# BLE-2541.net
KiCad netlist of a schematic drawn in Altium Designer
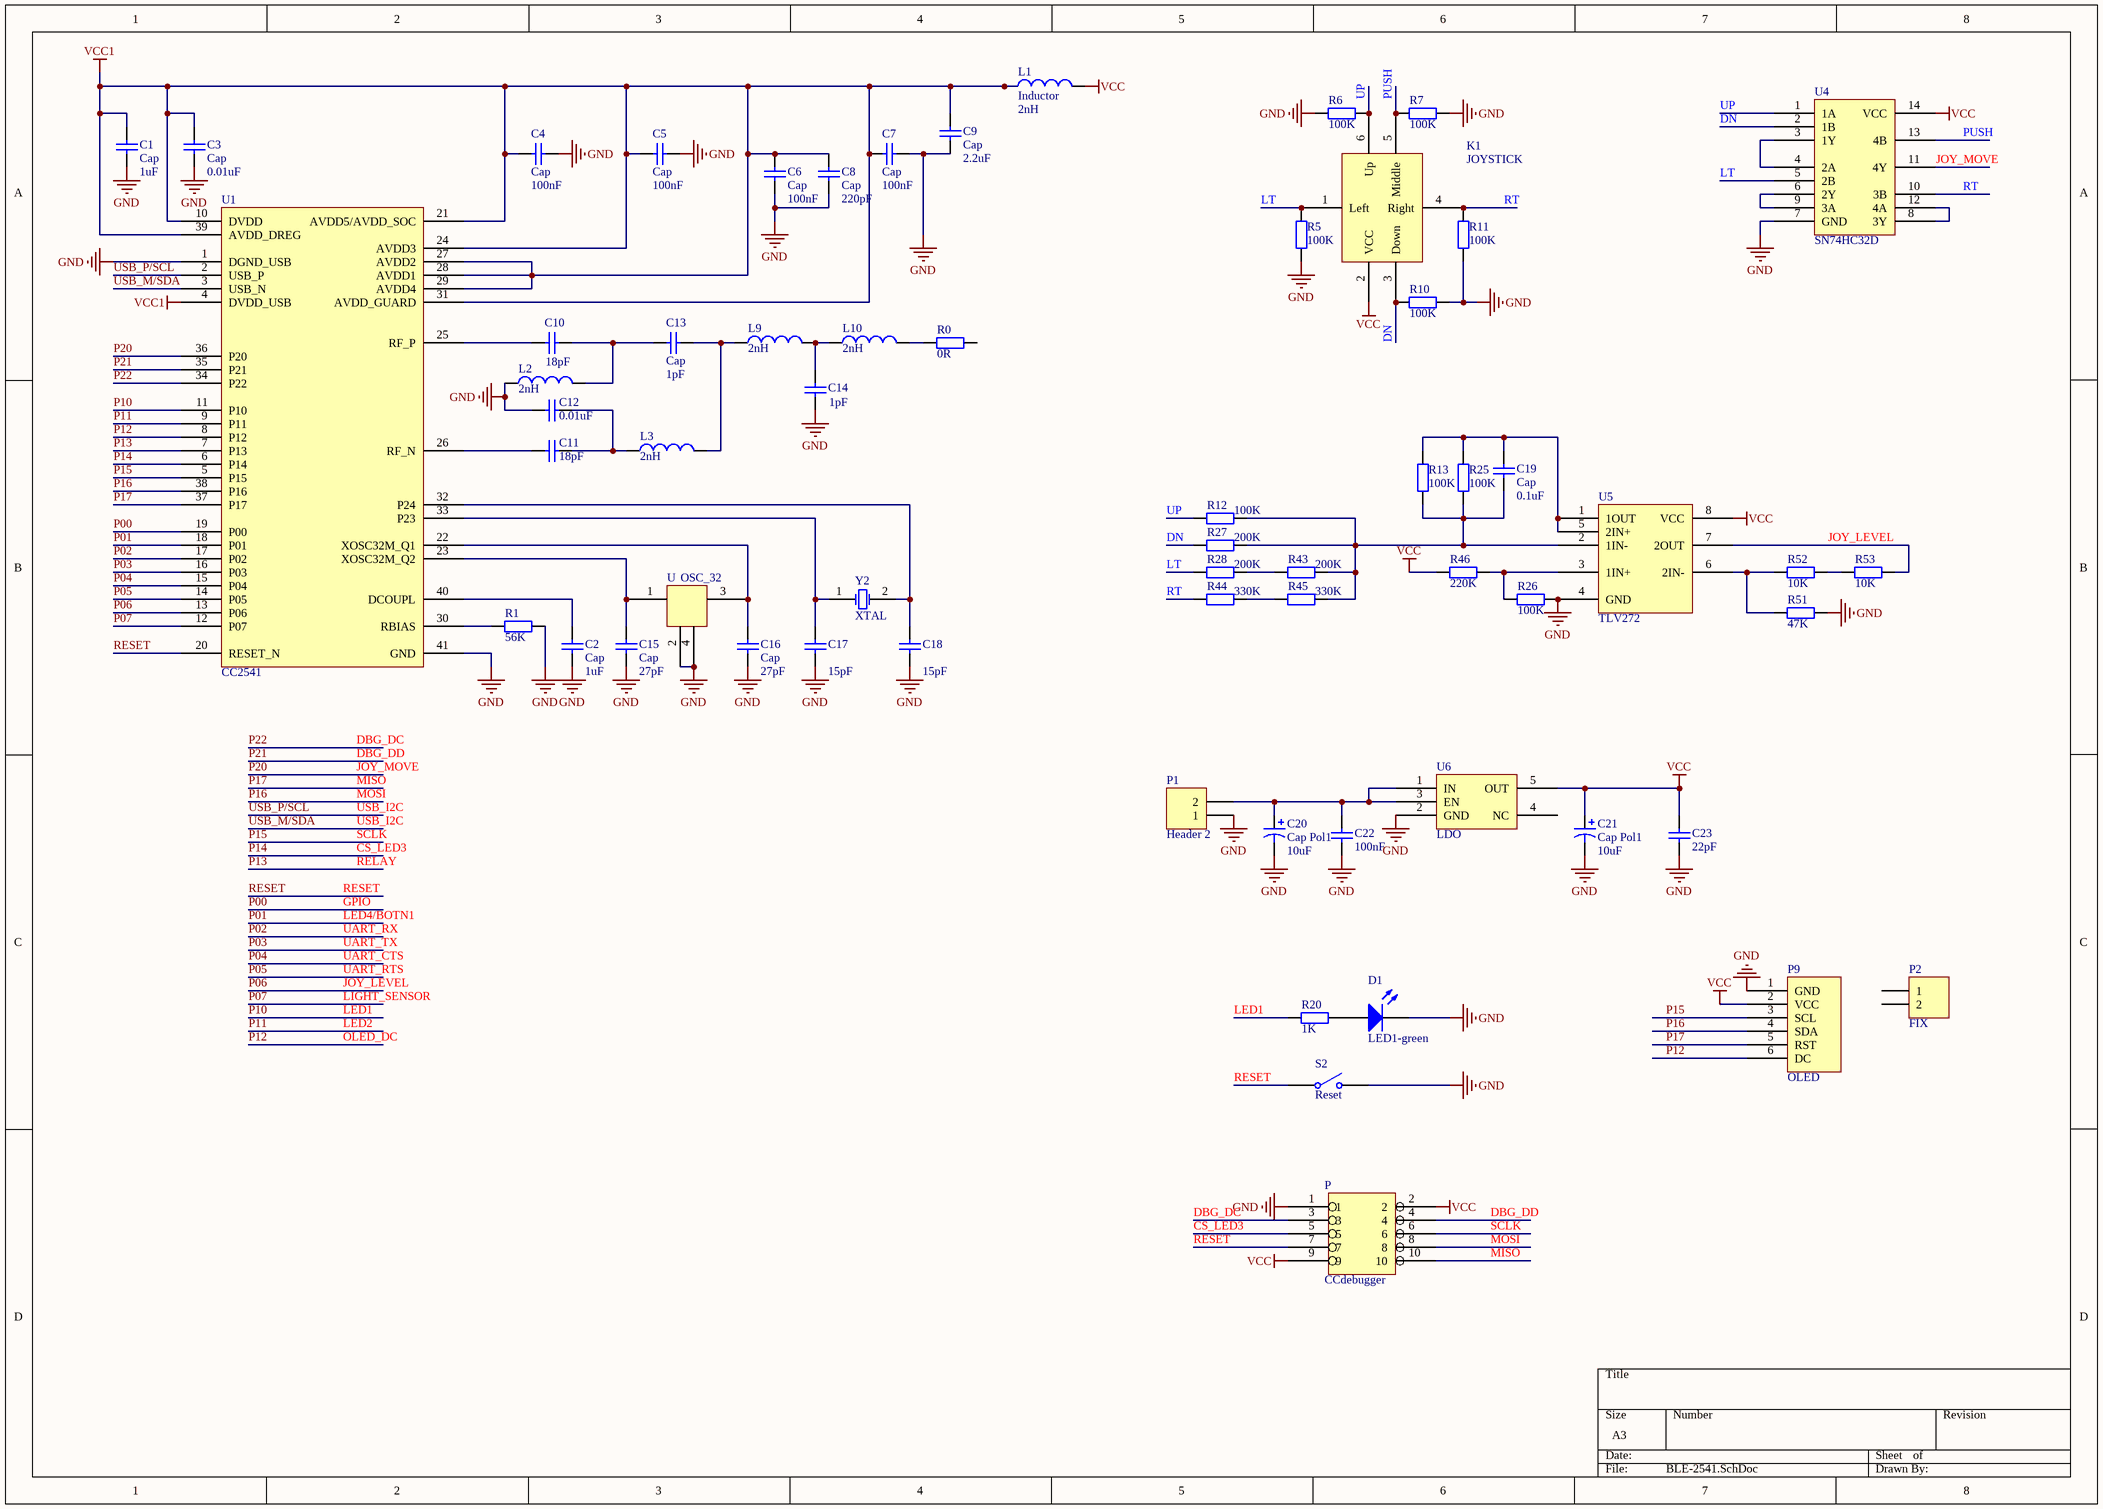
[diagram p0: BLE-2541.SchDoc]

(export (version "E")
  (design (tool "Eeschema 10.0.6"))
  (components
    (comp (ref "C1")
      (value "Cap")
      (footprint "RAD-0.3")
      (description "Capacitor")
      (fields (field (name "ALTIUM_VALUE") "1uF") (field (name "PUBLISHER") "Altium Limited"))
      (libsource (lib "Miscellaneous Devices") (part "Cap"))
    )
    (comp (ref "C2")
      (value "Cap")
      (footprint "RAD-0.3")
      (description "Capacitor")
      (fields (field (name "ALTIUM_VALUE") "1uF") (field (name "PUBLISHER") "Altium Limited"))
      (libsource (lib "Miscellaneous Devices") (part "Cap"))
    )
    (comp (ref "C3")
      (value "Cap")
      (footprint "RAD-0.3")
      (description "Capacitor")
      (fields (field (name "ALTIUM_VALUE") "0.01uF") (field (name "PUBLISHER") "Altium Limited"))
      (libsource (lib "Miscellaneous Devices") (part "Cap"))
    )
    (comp (ref "C4")
      (value "Cap")
      (footprint "RAD-0.3")
      (description "Capacitor")
      (fields (field (name "ALTIUM_VALUE") "100nF") (field (name "PUBLISHER") "Altium Limited"))
      (libsource (lib "Miscellaneous Devices") (part "Cap"))
    )
    (comp (ref "C5")
      (value "Cap")
      (footprint "RAD-0.3")
      (description "Capacitor")
      (fields (field (name "ALTIUM_VALUE") "100nF") (field (name "PUBLISHER") "Altium Limited"))
      (libsource (lib "Miscellaneous Devices") (part "Cap"))
    )
    (comp (ref "C6")
      (value "Cap")
      (footprint "RAD-0.3")
      (description "Capacitor")
      (fields (field (name "ALTIUM_VALUE") "100nF") (field (name "PUBLISHER") "Altium Limited"))
      (libsource (lib "Miscellaneous Devices") (part "Cap"))
    )
    (comp (ref "C7")
      (value "Cap")
      (footprint "RAD-0.3")
      (description "Capacitor")
      (fields (field (name "ALTIUM_VALUE") "100nF") (field (name "PUBLISHER") "Altium Limited"))
      (libsource (lib "Miscellaneous Devices") (part "Cap"))
    )
    (comp (ref "C8")
      (value "Cap")
      (footprint "RAD-0.3")
      (description "Capacitor")
      (fields (field (name "ALTIUM_VALUE") "220pF") (field (name "PUBLISHER") "Altium Limited"))
      (libsource (lib "Miscellaneous Devices") (part "Cap"))
    )
    (comp (ref "C9")
      (value "Cap")
      (footprint "RAD-0.3")
      (description "Capacitor")
      (fields (field (name "ALTIUM_VALUE") "2.2uF") (field (name "PUBLISHER") "Altium Limited"))
      (libsource (lib "Miscellaneous Devices") (part "Cap"))
    )
    (comp (ref "C10")
      (value "18pF")
      (footprint "RAD-0.3")
      (description "Capacitor")
      (fields (field (name "Comment") "Cap") (field (name "PUBLISHER") "Altium Limited"))
      (libsource (lib "Miscellaneous Devices") (part "Cap"))
    )
    (comp (ref "C11")
      (value "18pF")
      (footprint "RAD-0.3")
      (description "Capacitor")
      (fields (field (name "Comment") "Cap") (field (name "PUBLISHER") "Altium Limited"))
      (libsource (lib "Miscellaneous Devices") (part "Cap"))
    )
    (comp (ref "C12")
      (value "0.01uF")
      (footprint "RAD-0.3")
      (description "Capacitor")
      (fields (field (name "Comment") "Cap") (field (name "PUBLISHER") "Altium Limited"))
      (libsource (lib "Miscellaneous Devices") (part "Cap"))
    )
    (comp (ref "C13")
      (value "Cap")
      (footprint "RAD-0.3")
      (description "Capacitor")
      (fields (field (name "ALTIUM_VALUE") "1pF") (field (name "PUBLISHER") "Altium Limited"))
      (libsource (lib "Miscellaneous Devices") (part "Cap"))
    )
    (comp (ref "C14")
      (value "1pF")
      (footprint "RAD-0.3")
      (description "Capacitor")
      (fields (field (name "Comment") "Cap") (field (name "PUBLISHER") "Altium Limited"))
      (libsource (lib "Miscellaneous Devices") (part "Cap"))
    )
    (comp (ref "C15")
      (value "Cap")
      (footprint "RAD-0.3")
      (description "Capacitor")
      (fields (field (name "ALTIUM_VALUE") "27pF") (field (name "PUBLISHER") "Altium Limited"))
      (libsource (lib "Miscellaneous Devices") (part "Cap"))
    )
    (comp (ref "C16")
      (value "Cap")
      (footprint "RAD-0.3")
      (description "Capacitor")
      (fields (field (name "ALTIUM_VALUE") "27pF") (field (name "PUBLISHER") "Altium Limited"))
      (libsource (lib "Miscellaneous Devices") (part "Cap"))
    )
    (comp (ref "C17")
      (value "15pF")
      (footprint "RAD-0.3")
      (description "Capacitor")
      (fields (field (name "Comment") "Cap") (field (name "PUBLISHER") "Altium Limited"))
      (libsource (lib "Miscellaneous Devices") (part "Cap"))
    )
    (comp (ref "C18")
      (value "15pF")
      (footprint "RAD-0.3")
      (description "Capacitor")
      (fields (field (name "Comment") "Cap") (field (name "PUBLISHER") "Altium Limited"))
      (libsource (lib "Miscellaneous Devices") (part "Cap"))
    )
    (comp (ref "C19")
      (value "Cap")
      (footprint "RAD-0.3")
      (description "Capacitor")
      (fields (field (name "ALTIUM_VALUE") "0.1uF") (field (name "PUBLISHER") "Altium Limited"))
      (libsource (lib "Miscellaneous Devices") (part "Cap"))
    )
    (comp (ref "C20")
      (value "Cap Pol1")
      (footprint "RB7.6-15")
      (description "Polarized Capacitor (Radial)")
      (fields (field (name "ALTIUM_VALUE") "10uF") (field (name "PUBLISHER") "Altium Limited"))
      (libsource (lib "Miscellaneous Devices") (part "Cap Pol1"))
    )
    (comp (ref "C21")
      (value "Cap Pol1")
      (footprint "RB7.6-15")
      (description "Polarized Capacitor (Radial)")
      (fields (field (name "ALTIUM_VALUE") "10uF") (field (name "PUBLISHER") "Altium Limited"))
      (libsource (lib "Miscellaneous Devices") (part "Cap Pol1"))
    )
    (comp (ref "C22")
      (value "100nF")
      (footprint "RAD-0.3")
      (description "Capacitor")
      (fields (field (name "Comment") "Cap") (field (name "PUBLISHER") "Altium Limited"))
      (libsource (lib "Miscellaneous Devices") (part "Cap"))
    )
    (comp (ref "C23")
      (value "22pF")
      (footprint "RAD-0.3")
      (description "Capacitor")
      (fields (field (name "Comment") "Cap") (field (name "PUBLISHER") "Altium Limited"))
      (libsource (lib "Miscellaneous Devices") (part "Cap"))
    )
    (comp (ref "D1")
      (value "LED1-green")
      (footprint "3.2X1.6X1.1")
      (description "Typical RED, GREEN, YELLOW, AMBER GaAs LED")
      (fields (field (name "PUBLISHER") "Altium Limited"))
      (libsource (lib "Miscellaneous Devices") (part "LED2"))
    )
    (comp (ref "K1") (value "JOYSTICK") (libsource (lib "Schlib1") (part "JOYSTICK")))
    (comp (ref "L1")
      (value "Inductor")
      (footprint "0402-A")
      (fields (field (name "ALTIUM_VALUE") "2nH") (field (name "PUBLISHER") "Altium Limited"))
      (libsource (lib "Miscellaneous Devices") (part "Inductor"))
    )
    (comp (ref "L2")
      (value "2nH")
      (footprint "0402-A")
      (description "Inductor")
      (fields (field (name "PUBLISHER") "Altium Limited"))
      (libsource (lib "Miscellaneous Devices") (part "Inductor"))
    )
    (comp (ref "L3")
      (value "2nH")
      (footprint "0402-A")
      (description "Inductor")
      (fields (field (name "PUBLISHER") "Altium Limited"))
      (libsource (lib "Miscellaneous Devices") (part "Inductor"))
    )
    (comp (ref "L9")
      (value "2nH")
      (footprint "0402-A")
      (description "Inductor")
      (fields (field (name "PUBLISHER") "Altium Limited"))
      (libsource (lib "Miscellaneous Devices") (part "Inductor"))
    )
    (comp (ref "L10")
      (value "2nH")
      (footprint "0402-A")
      (description "Inductor")
      (fields (field (name "PUBLISHER") "Altium Limited"))
      (libsource (lib "Miscellaneous Devices") (part "Inductor"))
    )
    (comp (ref "P")
      (value "CCdebugger")
      (footprint "M-IDC10")
      (libsource (lib "Schlib1") (part "CCdebugger"))
    )
    (comp (ref "P1")
      (value "Header 2")
      (footprint "HDR1X2")
      (description "Header, 2-Pin")
      (fields (field (name "PUBLISHER") "Altium Limited"))
      (libsource (lib "Miscellaneous Connectors") (part "Header 2"))
    )
    (comp (ref "P2")
      (value "FIX")
      (footprint "HDR1X2")
      (description "Header, 2-Pin")
      (fields (field (name "PUBLISHER") "Altium Limited"))
      (libsource (lib "") (part "Header 2_1"))
    )
    (comp (ref "P9") (value "OLED") (footprint "M-SIP6") (libsource (lib "Schlib1") (part "OLED")))
    (comp (ref "R0")
      (value "0R")
      (footprint "AXIAL-0.4")
      (description "Resistor")
      (fields (field (name "Comment") "Res2") (field (name "PUBLISHER") "Altium Limited"))
      (libsource (lib "") (part "Res2_1"))
    )
    (comp (ref "R1")
      (value "56K")
      (footprint "AXIAL-0.4")
      (description "Resistor")
      (fields (field (name "Comment") "Res2") (field (name "PUBLISHER") "Altium Limited"))
      (libsource (lib "") (part "Res2_1"))
    )
    (comp (ref "R5")
      (value "100K")
      (footprint "AXIAL-0.4")
      (description "Resistor")
      (fields (field (name "Comment") "Res2") (field (name "PUBLISHER") "Altium Limited"))
      (libsource (lib "Miscellaneous Devices") (part "Res2"))
    )
    (comp (ref "R6")
      (value "100K")
      (footprint "AXIAL-0.4")
      (description "Resistor")
      (fields (field (name "Comment") "Res2") (field (name "PUBLISHER") "Altium Limited"))
      (libsource (lib "") (part "Res2_1"))
    )
    (comp (ref "R7")
      (value "100K")
      (footprint "AXIAL-0.4")
      (description "Resistor")
      (fields (field (name "Comment") "Res2") (field (name "PUBLISHER") "Altium Limited"))
      (libsource (lib "") (part "Res2_1"))
    )
    (comp (ref "R10")
      (value "100K")
      (footprint "AXIAL-0.4")
      (description "Resistor")
      (fields (field (name "Comment") "Res2") (field (name "PUBLISHER") "Altium Limited"))
      (libsource (lib "") (part "Res2_1"))
    )
    (comp (ref "R11")
      (value "100K")
      (footprint "AXIAL-0.4")
      (description "Resistor")
      (fields (field (name "Comment") "Res2") (field (name "PUBLISHER") "Altium Limited"))
      (libsource (lib "") (part "Res2_2"))
    )
    (comp (ref "R12")
      (value "100K")
      (footprint "AXIAL-0.4")
      (description "Resistor")
      (fields (field (name "Comment") "Res2") (field (name "PUBLISHER") "Altium Limited"))
      (libsource (lib "") (part "Res2_1"))
    )
    (comp (ref "R13")
      (value "100K")
      (footprint "AXIAL-0.4")
      (description "Resistor")
      (fields (field (name "Comment") "Res2") (field (name "PUBLISHER") "Altium Limited"))
      (libsource (lib "Miscellaneous Devices") (part "Res2"))
    )
    (comp (ref "R20")
      (value "1K")
      (footprint "AXIAL-0.4")
      (description "Resistor")
      (fields (field (name "Comment") "Res2") (field (name "PUBLISHER") "Altium Limited"))
      (libsource (lib "") (part "Res2_1"))
    )
    (comp (ref "R25")
      (value "100K")
      (footprint "AXIAL-0.4")
      (description "Resistor")
      (fields (field (name "Comment") "Res2") (field (name "PUBLISHER") "Altium Limited"))
      (libsource (lib "Miscellaneous Devices") (part "Res2"))
    )
    (comp (ref "R26")
      (value "100K")
      (footprint "AXIAL-0.4")
      (description "Resistor")
      (fields (field (name "Comment") "Res2") (field (name "PUBLISHER") "Altium Limited"))
      (libsource (lib "") (part "Res2_1"))
    )
    (comp (ref "R27")
      (value "200K")
      (footprint "AXIAL-0.4")
      (description "Resistor")
      (fields (field (name "Comment") "Res2") (field (name "PUBLISHER") "Altium Limited"))
      (libsource (lib "") (part "Res2_1"))
    )
    (comp (ref "R28")
      (value "200K")
      (footprint "AXIAL-0.4")
      (description "Resistor")
      (fields (field (name "Comment") "Res2") (field (name "PUBLISHER") "Altium Limited"))
      (libsource (lib "") (part "Res2_1"))
    )
    (comp (ref "R43")
      (value "200K")
      (footprint "AXIAL-0.4")
      (description "Resistor")
      (fields (field (name "Comment") "Res2") (field (name "PUBLISHER") "Altium Limited"))
      (libsource (lib "") (part "Res2_1"))
    )
    (comp (ref "R44")
      (value "330K")
      (footprint "AXIAL-0.4")
      (description "Resistor")
      (fields (field (name "Comment") "Res2") (field (name "PUBLISHER") "Altium Limited"))
      (libsource (lib "") (part "Res2_1"))
    )
    (comp (ref "R45")
      (value "330K")
      (footprint "AXIAL-0.4")
      (description "Resistor")
      (fields (field (name "Comment") "Res2") (field (name "PUBLISHER") "Altium Limited"))
      (libsource (lib "") (part "Res2_1"))
    )
    (comp (ref "R46")
      (value "220K")
      (footprint "AXIAL-0.4")
      (description "Resistor")
      (fields (field (name "Comment") "Res2") (field (name "PUBLISHER") "Altium Limited"))
      (libsource (lib "") (part "Res2_1"))
    )
    (comp (ref "R51")
      (value "47K")
      (footprint "AXIAL-0.4")
      (description "Resistor")
      (fields (field (name "Comment") "Res2") (field (name "PUBLISHER") "Altium Limited"))
      (libsource (lib "") (part "Res2_1"))
    )
    (comp (ref "R52")
      (value "10K")
      (footprint "AXIAL-0.4")
      (description "Resistor")
      (fields (field (name "Comment") "Res2") (field (name "PUBLISHER") "Altium Limited"))
      (libsource (lib "") (part "Res2_1"))
    )
    (comp (ref "R53")
      (value "10K")
      (footprint "AXIAL-0.4")
      (description "Resistor")
      (fields (field (name "Comment") "Res2") (field (name "PUBLISHER") "Altium Limited"))
      (libsource (lib "") (part "Res2_1"))
    )
    (comp (ref "S2")
      (value "Reset")
      (footprint "SPST-2")
      (description "Single-Pole, Single-Throw Switch")
      (fields (field (name "PUBLISHER") "Altium Limited"))
      (libsource (lib "Miscellaneous Devices") (part "SW-SPST"))
    )
    (comp (ref "U") (value "OSC_32") (libsource (lib "Schlib1") (part "OSC_32")))
    (comp (ref "U1") (value "CC2541") (footprint "CC254x_QFN") (libsource (lib "Schlib1") (part "CC2541")))
    (comp (ref "U4") (value "SN74HC32D") (footprint "SOIC14") (libsource (lib "Schlib1") (part "SN74HC32D")))
    (comp (ref "U5") (value "TLV272") (footprint "SOIC8") (libsource (lib "Schlib1") (part "TLV272")))
    (comp (ref "U6") (value "LDO") (libsource (lib "Schlib1") (part "LDO")))
    (comp (ref "Y2")
      (value "XTAL")
      (footprint "R38")
      (description "Crystal Oscillator")
      (fields (field (name "PUBLISHER") "Altium Limited"))
      (libsource (lib "Miscellaneous Devices") (part "XTAL"))
    )
  )
  (nets
    (net (code "1") (name "/CS_LED3") (class "Default")
      (node (ref "P") (pin "5") (pinfunction "5_5") (pintype "passive"))
      (node (ref "U1") (pin "6") (pinfunction "P14_6") (pintype "passive"))
    )
    (net (code "2") (name "/DBG_DC") (class "Default")
      (node (ref "P") (pin "3") (pinfunction "3_3") (pintype "passive"))
      (node (ref "U1") (pin "34") (pinfunction "P22_34") (pintype "passive"))
    )
    (net (code "3") (name "/DBG_DD") (class "Default")
      (node (ref "P") (pin "4") (pinfunction "4_4") (pintype "passive"))
      (node (ref "U1") (pin "35") (pinfunction "P21_35") (pintype "passive"))
    )
    (net (code "4") (name "/DN") (class "Default")
      (node (ref "K1") (pin "3") (pinfunction "Down_3") (pintype "passive"))
      (node (ref "R10") (pin "1") (pinfunction "1_1") (pintype "passive"))
      (node (ref "R27") (pin "1") (pinfunction "1_1") (pintype "passive"))
      (node (ref "U4") (pin "2") (pinfunction "1B_2") (pintype "passive"))
    )
    (net (code "5") (name "/GPIO") (class "Default")
      (node (ref "U1") (pin "19") (pinfunction "P00_19") (pintype "passive"))
    )
    (net (code "6") (name "/JOY_LEVEL") (class "Default")
      (node (ref "R53") (pin "2") (pinfunction "2_2") (pintype "passive"))
      (node (ref "U1") (pin "13") (pinfunction "P06_13") (pintype "passive"))
      (node (ref "U5") (pin "7") (pinfunction "2OUT_7") (pintype "passive"))
    )
    (net (code "7") (name "/JOY_MOVE") (class "Default")
      (node (ref "U1") (pin "36") (pinfunction "P20_36") (pintype "passive"))
      (node (ref "U4") (pin "11") (pinfunction "4Y_11") (pintype "passive"))
    )
    (net (code "8") (name "/LED1") (class "Default")
      (node (ref "R20") (pin "1") (pinfunction "1_1") (pintype "passive"))
      (node (ref "U1") (pin "11") (pinfunction "P10_11") (pintype "passive"))
    )
    (net (code "9") (name "/LED2") (class "Default")
      (node (ref "U1") (pin "9") (pinfunction "P11_9") (pintype "passive"))
    )
    (net (code "10") (name "/LED4{slash}BOTN1") (class "Default")
      (node (ref "U1") (pin "18") (pinfunction "P01_18") (pintype "passive"))
    )
    (net (code "11") (name "/LIGHT_SENSOR") (class "Default")
      (node (ref "U1") (pin "12") (pinfunction "P07_12") (pintype "passive"))
    )
    (net (code "12") (name "/LT") (class "Default")
      (node (ref "K1") (pin "1") (pinfunction "Left_1") (pintype "passive"))
      (node (ref "R28") (pin "1") (pinfunction "1_1") (pintype "passive"))
      (node (ref "R5") (pin "2") (pinfunction "2_2") (pintype "passive"))
      (node (ref "U4") (pin "5") (pinfunction "2B_5") (pintype "passive"))
    )
    (net (code "13") (name "/MISO") (class "Default")
      (node (ref "P") (pin "10") (pinfunction "10_10") (pintype "passive"))
      (node (ref "P9") (pin "5") (pinfunction "RST_5") (pintype "passive"))
      (node (ref "U1") (pin "37") (pinfunction "P17_37") (pintype "passive"))
    )
    (net (code "14") (name "/MOSI") (class "Default")
      (node (ref "P") (pin "8") (pinfunction "8_8") (pintype "passive"))
      (node (ref "P9") (pin "4") (pinfunction "SDA_4") (pintype "passive"))
      (node (ref "U1") (pin "38") (pinfunction "P16_38") (pintype "passive"))
    )
    (net (code "15") (name "/OLED_DC") (class "Default")
      (node (ref "P9") (pin "6") (pinfunction "DC_6") (pintype "passive"))
      (node (ref "U1") (pin "8") (pinfunction "P12_8") (pintype "passive"))
    )
    (net (code "16") (name "/P02") (class "Default")
      (node (ref "U1") (pin "17") (pinfunction "P02_17") (pintype "passive"))
    )
    (net (code "17") (name "/P03") (class "Default")
      (node (ref "U1") (pin "16") (pinfunction "P03_16") (pintype "passive"))
    )
    (net (code "18") (name "/P04") (class "Default")
      (node (ref "U1") (pin "15") (pinfunction "P04_15") (pintype "passive"))
    )
    (net (code "19") (name "/P05") (class "Default")
      (node (ref "U1") (pin "14") (pinfunction "P05_14") (pintype "passive"))
    )
    (net (code "20") (name "/P13") (class "Default")
      (node (ref "U1") (pin "7") (pinfunction "P13_7") (pintype "passive"))
    )
    (net (code "21") (name "/P15") (class "Default")
      (node (ref "P") (pin "6") (pinfunction "6_6") (pintype "passive"))
      (node (ref "P9") (pin "3") (pinfunction "SCL_3") (pintype "passive"))
      (node (ref "U1") (pin "5") (pinfunction "P15_5") (pintype "passive"))
    )
    (net (code "22") (name "/PUSH") (class "Default")
      (node (ref "K1") (pin "5") (pinfunction "Middle_5") (pintype "passive"))
      (node (ref "R7") (pin "1") (pinfunction "1_1") (pintype "passive"))
      (node (ref "U4") (pin "13") (pinfunction "4B_13") (pintype "passive"))
    )
    (net (code "23") (name "/RESET") (class "Default")
      (node (ref "P") (pin "7") (pinfunction "7_7") (pintype "passive"))
      (node (ref "S2") (pin "1") (pinfunction "COMMON_1") (pintype "passive"))
      (node (ref "U1") (pin "20") (pinfunction "RESET_N_20") (pintype "passive"))
    )
    (net (code "24") (name "/RT") (class "Default")
      (node (ref "K1") (pin "4") (pinfunction "Right_4") (pintype "passive"))
      (node (ref "R11") (pin "1") (pinfunction "1_1") (pintype "passive"))
      (node (ref "R44") (pin "1") (pinfunction "1_1") (pintype "passive"))
      (node (ref "U4") (pin "10") (pinfunction "3B_10") (pintype "passive"))
    )
    (net (code "25") (name "/UP") (class "Default")
      (node (ref "K1") (pin "6") (pinfunction "Up_6") (pintype "passive"))
      (node (ref "R12") (pin "1") (pinfunction "1_1") (pintype "passive"))
      (node (ref "R6") (pin "2") (pinfunction "2_2") (pintype "passive"))
      (node (ref "U4") (pin "1") (pinfunction "1A_1") (pintype "passive"))
    )
    (net (code "26") (name "/USB_I2C") (class "Default")
      (node (ref "U1") (pin "2") (pinfunction "USB_P_2") (pintype "passive"))
      (node (ref "U1") (pin "3") (pinfunction "USB_N_3") (pintype "passive"))
    )
    (net (code "27") (name "GND") (class "Default")
      (node (ref "C1") (pin "1") (pinfunction "1_1") (pintype "passive"))
      (node (ref "C12") (pin "2") (pinfunction "2_2") (pintype "passive"))
      (node (ref "C14") (pin "1") (pinfunction "1_1") (pintype "passive"))
      (node (ref "C15") (pin "1") (pinfunction "1_1") (pintype "passive"))
      (node (ref "C16") (pin "1") (pinfunction "1_1") (pintype "passive"))
      (node (ref "C17") (pin "2") (pinfunction "2_2") (pintype "passive"))
      (node (ref "C18") (pin "2") (pinfunction "2_2") (pintype "passive"))
      (node (ref "C2") (pin "1") (pinfunction "1_1") (pintype "passive"))
      (node (ref "C20") (pin "2") (pinfunction "2_2") (pintype "passive"))
      (node (ref "C21") (pin "2") (pinfunction "2_2") (pintype "passive"))
      (node (ref "C22") (pin "1") (pinfunction "1_1") (pintype "passive"))
      (node (ref "C23") (pin "1") (pinfunction "1_1") (pintype "passive"))
      (node (ref "C3") (pin "1") (pinfunction "1_1") (pintype "passive"))
      (node (ref "C4") (pin "1") (pinfunction "1_1") (pintype "passive"))
      (node (ref "C5") (pin "1") (pinfunction "1_1") (pintype "passive"))
      (node (ref "C6") (pin "2") (pinfunction "2_2") (pintype "passive"))
      (node (ref "C7") (pin "1") (pinfunction "1_1") (pintype "passive"))
      (node (ref "C8") (pin "2") (pinfunction "2_2") (pintype "passive"))
      (node (ref "C9") (pin "2") (pinfunction "2_2") (pintype "passive"))
      (node (ref "D1") (pin "2") (pinfunction "K_2") (pintype "passive"))
      (node (ref "L2") (pin "1") (pinfunction "1_1") (pintype "passive"))
      (node (ref "P") (pin "1") (pinfunction "1_1") (pintype "passive"))
      (node (ref "P1") (pin "1") (pinfunction "1_1") (pintype "passive"))
      (node (ref "P9") (pin "1") (pinfunction "GND_1") (pintype "passive"))
      (node (ref "R1") (pin "2") (pinfunction "2_2") (pintype "passive"))
      (node (ref "R10") (pin "2") (pinfunction "2_2") (pintype "passive"))
      (node (ref "R11") (pin "2") (pinfunction "2_2") (pintype "passive"))
      (node (ref "R26") (pin "2") (pinfunction "2_2") (pintype "passive"))
      (node (ref "R5") (pin "1") (pinfunction "1_1") (pintype "passive"))
      (node (ref "R51") (pin "2") (pinfunction "2_2") (pintype "passive"))
      (node (ref "R6") (pin "1") (pinfunction "1_1") (pintype "passive"))
      (node (ref "R7") (pin "2") (pinfunction "2_2") (pintype "passive"))
      (node (ref "S2") (pin "2") (pinfunction "NO_2") (pintype "passive"))
      (node (ref "U") (pin "2") (pinfunction "2_2") (pintype "passive"))
      (node (ref "U") (pin "4") (pinfunction "4_4") (pintype "passive"))
      (node (ref "U1") (pin "1") (pinfunction "DGND_USB_1") (pintype "passive"))
      (node (ref "U1") (pin "41") (pinfunction "GND_41") (pintype "passive"))
      (node (ref "U4") (pin "7") (pinfunction "GND_7") (pintype "passive"))
      (node (ref "U5") (pin "4") (pinfunction "GND_4") (pintype "passive"))
      (node (ref "U6") (pin "2") (pinfunction "GND_2") (pintype "passive"))
    )
    (net (code "28") (name "Net-(C10-Pad1)") (class "Default")
      (node (ref "C10") (pin "1") (pinfunction "1_1") (pintype "passive"))
      (node (ref "C13") (pin "2") (pinfunction "2_2") (pintype "passive"))
      (node (ref "L2") (pin "2") (pinfunction "2_2") (pintype "passive"))
    )
    (net (code "29") (name "Net-(C11-Pad1)") (class "Default")
      (node (ref "C11") (pin "1") (pinfunction "1_1") (pintype "passive"))
      (node (ref "C12") (pin "1") (pinfunction "1_1") (pintype "passive"))
      (node (ref "L3") (pin "1") (pinfunction "1_1") (pintype "passive"))
    )
    (net (code "30") (name "Net-(C13-Pad1)") (class "Default")
      (node (ref "C13") (pin "1") (pinfunction "1_1") (pintype "passive"))
      (node (ref "L3") (pin "2") (pinfunction "2_2") (pintype "passive"))
      (node (ref "L9") (pin "1") (pinfunction "1_1") (pintype "passive"))
    )
    (net (code "31") (name "Net-(C14-Pad2)") (class "Default")
      (node (ref "C14") (pin "2") (pinfunction "2_2") (pintype "passive"))
      (node (ref "L10") (pin "1") (pinfunction "1_1") (pintype "passive"))
      (node (ref "L9") (pin "2") (pinfunction "2_2") (pintype "passive"))
    )
    (net (code "32") (name "Net-(D1-A)") (class "Default")
      (node (ref "D1") (pin "1") (pinfunction "A_1") (pintype "passive"))
      (node (ref "R20") (pin "2") (pinfunction "2_2") (pintype "passive"))
    )
    (net (code "33") (name "Net-(L10-Pad2)") (class "Default")
      (node (ref "L10") (pin "2") (pinfunction "2_2") (pintype "passive"))
      (node (ref "R0") (pin "1") (pinfunction "1_1") (pintype "passive"))
    )
    (net (code "34") (name "Net-(R28-Pad2)") (class "Default")
      (node (ref "R28") (pin "2") (pinfunction "2_2") (pintype "passive"))
      (node (ref "R43") (pin "1") (pinfunction "1_1") (pintype "passive"))
    )
    (net (code "35") (name "Net-(R44-Pad2)") (class "Default")
      (node (ref "R44") (pin "2") (pinfunction "2_2") (pintype "passive"))
      (node (ref "R45") (pin "1") (pinfunction "1_1") (pintype "passive"))
    )
    (net (code "36") (name "Net-(R52-Pad2)") (class "Default")
      (node (ref "R52") (pin "2") (pinfunction "2_2") (pintype "passive"))
      (node (ref "R53") (pin "1") (pinfunction "1_1") (pintype "passive"))
    )
    (net (code "37") (name "Net-(U1-DCOUPL)") (class "Default")
      (node (ref "C2") (pin "2") (pinfunction "2_2") (pintype "passive"))
      (node (ref "U1") (pin "40") (pinfunction "DCOUPL_40") (pintype "passive"))
    )
    (net (code "38") (name "Net-(U1-P23)") (class "Default")
      (node (ref "C17") (pin "1") (pinfunction "1_1") (pintype "passive"))
      (node (ref "U1") (pin "33") (pinfunction "P23_33") (pintype "passive"))
      (node (ref "Y2") (pin "1") (pinfunction "OSC1_1") (pintype "passive"))
    )
    (net (code "39") (name "Net-(U1-P24)") (class "Default")
      (node (ref "C18") (pin "1") (pinfunction "1_1") (pintype "passive"))
      (node (ref "U1") (pin "32") (pinfunction "P24_32") (pintype "passive"))
      (node (ref "Y2") (pin "2") (pinfunction "OSC2_2") (pintype "passive"))
    )
    (net (code "40") (name "Net-(U1-RBIAS)") (class "Default")
      (node (ref "R1") (pin "1") (pinfunction "1_1") (pintype "passive"))
      (node (ref "U1") (pin "30") (pinfunction "RBIAS_30") (pintype "passive"))
    )
    (net (code "41") (name "Net-(U1-RF_N)") (class "Default")
      (node (ref "C11") (pin "2") (pinfunction "2_2") (pintype "passive"))
      (node (ref "U1") (pin "26") (pinfunction "RF_N_26") (pintype "passive"))
    )
    (net (code "42") (name "Net-(U1-RF_P)") (class "Default")
      (node (ref "C10") (pin "2") (pinfunction "2_2") (pintype "passive"))
      (node (ref "U1") (pin "25") (pinfunction "RF_P_25") (pintype "passive"))
    )
    (net (code "43") (name "Net-(U1-XOSC32M_Q1)") (class "Default")
      (node (ref "C16") (pin "2") (pinfunction "2_2") (pintype "passive"))
      (node (ref "U") (pin "3") (pinfunction "3_3") (pintype "passive"))
      (node (ref "U1") (pin "22") (pinfunction "XOSC32M_Q1_22") (pintype "passive"))
    )
    (net (code "44") (name "Net-(U1-XOSC32M_Q2)") (class "Default")
      (node (ref "C15") (pin "2") (pinfunction "2_2") (pintype "passive"))
      (node (ref "U") (pin "1") (pinfunction "1_1") (pintype "passive"))
      (node (ref "U1") (pin "23") (pinfunction "XOSC32M_Q2_23") (pintype "passive"))
    )
    (net (code "45") (name "Net-(U4-1Y)") (class "Default")
      (node (ref "U4") (pin "3") (pinfunction "1Y_3") (pintype "passive"))
      (node (ref "U4") (pin "4") (pinfunction "2A_4") (pintype "passive"))
    )
    (net (code "46") (name "Net-(U4-2Y)") (class "Default")
      (node (ref "U4") (pin "6") (pinfunction "2Y_6") (pintype "passive"))
      (node (ref "U4") (pin "9") (pinfunction "3A_9") (pintype "passive"))
    )
    (net (code "47") (name "Net-(U4-3Y)") (class "Default")
      (node (ref "U4") (pin "12") (pinfunction "4A_12") (pintype "passive"))
      (node (ref "U4") (pin "8") (pinfunction "3Y_8") (pintype "passive"))
    )
    (net (code "48") (name "Net-(U5-1IN+)") (class "Default")
      (node (ref "R26") (pin "1") (pinfunction "1_1") (pintype "passive"))
      (node (ref "R46") (pin "2") (pinfunction "2_2") (pintype "passive"))
      (node (ref "U5") (pin "3") (pinfunction "1IN+_3") (pintype "passive"))
    )
    (net (code "49") (name "Net-(U5-1IN-)") (class "Default")
      (node (ref "C19") (pin "1") (pinfunction "1_1") (pintype "passive"))
      (node (ref "R12") (pin "2") (pinfunction "2_2") (pintype "passive"))
      (node (ref "R13") (pin "1") (pinfunction "1_1") (pintype "passive"))
      (node (ref "R25") (pin "1") (pinfunction "1_1") (pintype "passive"))
      (node (ref "R27") (pin "2") (pinfunction "2_2") (pintype "passive"))
      (node (ref "R43") (pin "2") (pinfunction "2_2") (pintype "passive"))
      (node (ref "R45") (pin "2") (pinfunction "2_2") (pintype "passive"))
      (node (ref "U5") (pin "2") (pinfunction "1IN-_2") (pintype "passive"))
    )
    (net (code "50") (name "Net-(U5-1OUT)") (class "Default")
      (node (ref "C19") (pin "2") (pinfunction "2_2") (pintype "passive"))
      (node (ref "R13") (pin "2") (pinfunction "2_2") (pintype "passive"))
      (node (ref "R25") (pin "2") (pinfunction "2_2") (pintype "passive"))
      (node (ref "U5") (pin "1") (pinfunction "1OUT_1") (pintype "passive"))
      (node (ref "U5") (pin "5") (pinfunction "2IN+_5") (pintype "passive"))
    )
    (net (code "51") (name "Net-(U5-2IN-)") (class "Default")
      (node (ref "R51") (pin "1") (pinfunction "1_1") (pintype "passive"))
      (node (ref "R52") (pin "1") (pinfunction "1_1") (pintype "passive"))
      (node (ref "U5") (pin "6") (pinfunction "2IN-_6") (pintype "passive"))
    )
    (net (code "52") (name "Net-(U6-EN)") (class "Default")
      (node (ref "C20") (pin "1") (pinfunction "1_1") (pintype "passive"))
      (node (ref "C22") (pin "2") (pinfunction "2_2") (pintype "passive"))
      (node (ref "P1") (pin "2") (pinfunction "2_2") (pintype "passive"))
      (node (ref "U6") (pin "1") (pinfunction "IN_1") (pintype "passive"))
      (node (ref "U6") (pin "3") (pinfunction "EN_3") (pintype "passive"))
    )
    (net (code "53") (name "VCC") (class "Default")
      (node (ref "C21") (pin "1") (pinfunction "1_1") (pintype "passive"))
      (node (ref "C23") (pin "2") (pinfunction "2_2") (pintype "passive"))
      (node (ref "K1") (pin "2") (pinfunction "VCC_2") (pintype "passive"))
      (node (ref "L1") (pin "2") (pinfunction "2_2") (pintype "passive"))
      (node (ref "P") (pin "2") (pinfunction "2_2") (pintype "passive"))
      (node (ref "P") (pin "9") (pinfunction "9_9") (pintype "passive"))
      (node (ref "P9") (pin "2") (pinfunction "VCC_2") (pintype "passive"))
      (node (ref "R46") (pin "1") (pinfunction "1_1") (pintype "passive"))
      (node (ref "U4") (pin "14") (pinfunction "VCC_14") (pintype "passive"))
      (node (ref "U5") (pin "8") (pinfunction "VCC_8") (pintype "passive"))
      (node (ref "U6") (pin "5") (pinfunction "OUT_5") (pintype "passive"))
    )
    (net (code "54") (name "VCC1") (class "Default")
      (node (ref "C1") (pin "2") (pinfunction "2_2") (pintype "passive"))
      (node (ref "C3") (pin "2") (pinfunction "2_2") (pintype "passive"))
      (node (ref "C4") (pin "2") (pinfunction "2_2") (pintype "passive"))
      (node (ref "C5") (pin "2") (pinfunction "2_2") (pintype "passive"))
      (node (ref "C6") (pin "1") (pinfunction "1_1") (pintype "passive"))
      (node (ref "C7") (pin "2") (pinfunction "2_2") (pintype "passive"))
      (node (ref "C8") (pin "1") (pinfunction "1_1") (pintype "passive"))
      (node (ref "C9") (pin "1") (pinfunction "1_1") (pintype "passive"))
      (node (ref "L1") (pin "1") (pinfunction "1_1") (pintype "passive"))
      (node (ref "U1") (pin "10") (pinfunction "DVDD_10") (pintype "passive"))
      (node (ref "U1") (pin "21") (pinfunction "AVDD5/AVDD_SOC_21") (pintype "passive"))
      (node (ref "U1") (pin "24") (pinfunction "AVDD3_24") (pintype "passive"))
      (node (ref "U1") (pin "27") (pinfunction "AVDD2_27") (pintype "passive"))
      (node (ref "U1") (pin "28") (pinfunction "AVDD1_28") (pintype "passive"))
      (node (ref "U1") (pin "29") (pinfunction "AVDD4_29") (pintype "passive"))
      (node (ref "U1") (pin "31") (pinfunction "AVDD_GUARD_31") (pintype "passive"))
      (node (ref "U1") (pin "39") (pinfunction "AVDD_DREG_39") (pintype "passive"))
      (node (ref "U1") (pin "4") (pinfunction "DVDD_USB_4") (pintype "passive"))
    )
    (net (code "55") (name "unconnected-(P2-Pad1)") (class "Default")
      (node (ref "P2") (pin "1") (pinfunction "1_1") (pintype "passive"))
    )
    (net (code "56") (name "unconnected-(P2-Pad2)") (class "Default")
      (node (ref "P2") (pin "2") (pinfunction "2_2") (pintype "passive"))
    )
    (net (code "57") (name "unconnected-(R0-Pad2)") (class "Default")
      (node (ref "R0") (pin "2") (pinfunction "2_2") (pintype "passive"))
    )
    (net (code "58") (name "unconnected-(U6-NC-Pad4)") (class "Default")
      (node (ref "U6") (pin "4") (pinfunction "NC_4") (pintype "passive"))
    )
  )
)
